# WatchDog.net
KiCad netlist of a schematic drawn in Altium Designer
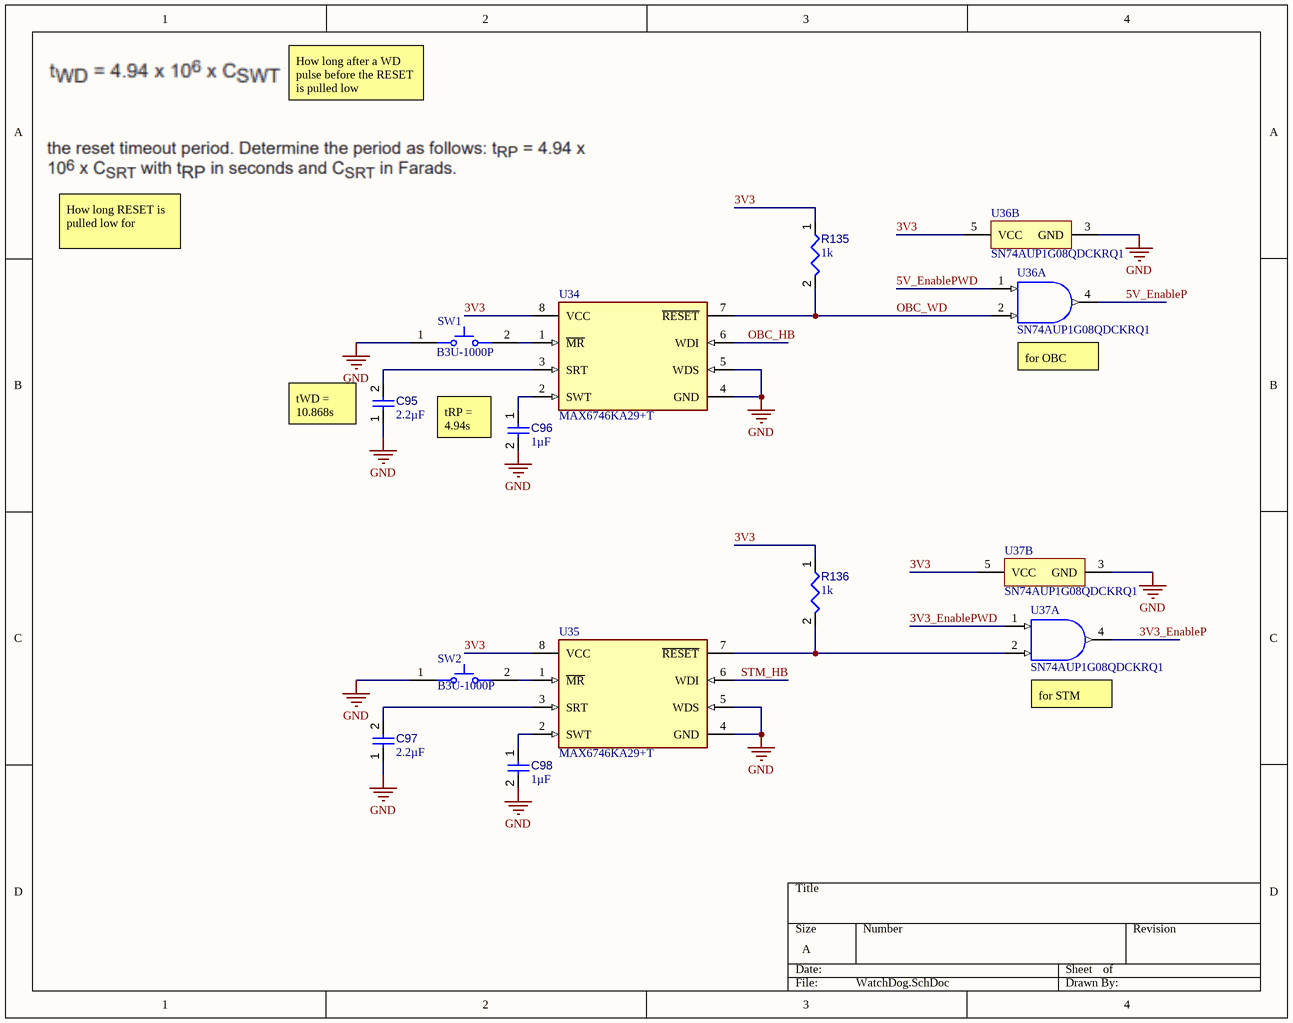
[diagram p0: WatchDog.SchDoc]

(export (version "E")
  (design (tool "Eeschema 10.0.6"))
  (components
    (comp (ref "C95")
      (value "2.2µF")
      (footprint "CAPC0402(1005)60_L")
      (description "Chip Capacitor, 2,2µF +/-20%, 10V, 0402, Thickness 0.6 mm")
      (fields (field (name "TOLERANCE") "10%") (field (name "Comment") "Capacitor 2,2µF +/-20% 10V 0402"))
      (libsource (lib "UGA SSRL Hardware Team") (part "CAP-NP-2"))
    )
    (comp (ref "C96")
      (value "1µF")
      (footprint "CAPC0603(1608)100_L")
      (description "Chip Capacitor, 1µF +/-40%, 50V, 0603, Thickness 1 mm")
      (fields (field (name "TOLERANCE") "10%") (field (name "Comment") "Capacitor 1µF +/-40% 50V 0603"))
      (libsource (lib "UGA SSRL Hardware Team") (part "CAP-NP-2"))
    )
    (comp (ref "C97")
      (value "2.2µF")
      (footprint "CAPC0402(1005)60_L")
      (description "Chip Capacitor, 2,2µF +/-20%, 10V, 0402, Thickness 0.6 mm")
      (fields (field (name "TOLERANCE") "10%") (field (name "Comment") "Capacitor 2,2µF +/-20% 10V 0402"))
      (libsource (lib "UGA SSRL Hardware Team") (part "CAP-NP-2"))
    )
    (comp (ref "C98")
      (value "1µF")
      (footprint "CAPC0603(1608)100_L")
      (description "Chip Capacitor, 1µF +/-40%, 50V, 0603, Thickness 1 mm")
      (fields (field (name "TOLERANCE") "10%") (field (name "Comment") "Capacitor 1µF +/-40% 50V 0603"))
      (libsource (lib "UGA SSRL Hardware Team") (part "CAP-NP-2"))
    )
    (comp (ref "R135")
      (value "1k")
      (footprint "RESC0805(2012)_L")
      (description "1K 0.125W 5% 0805 (2012 Metric)  SMD")
      (fields (field (name "TOLERANCE") "5%") (field (name "POWER") "125mW"))
      (libsource (lib "UGA SSRL Hardware Team") (part "1KR5J"))
    )
    (comp (ref "R136")
      (value "1k")
      (footprint "RESC0805(2012)_L")
      (description "1K 0.125W 5% 0805 (2012 Metric)  SMD")
      (fields (field (name "TOLERANCE") "5%") (field (name "POWER") "125mW"))
      (libsource (lib "UGA SSRL Hardware Team") (part "1KR5J"))
    )
    (comp (ref "SW1")
      (value "B3U-1000P")
      (footprint "OMRON-B3U-1000_V")
      (description "Tactile Switch, SPST-NO, 0.05 A, 12 V, -25 to 70 degC, 2-Pin SMD, RoHS, Tape and Reel")
      (fields (field (name "MANUFACTURER") "Omron Electronic Components"))
      (libsource (lib "UGA SSRL Hardware Team") (part "SW-SPST-NO-2"))
    )
    (comp (ref "SW2")
      (value "B3U-1000P")
      (footprint "OMRON-B3U-1000_V")
      (description "Tactile Switch, SPST-NO, 0.05 A, 12 V, -25 to 70 degC, 2-Pin SMD, RoHS, Tape and Reel")
      (fields (field (name "MANUFACTURER") "Omron Electronic Components"))
      (libsource (lib "UGA SSRL Hardware Team") (part "SW-SPST-NO-2"))
    )
    (comp (ref "U34")
      (value "MAX6746KA29+T")
      (footprint "FP-K8-5-IPC_C")
      (description "Power Supply Management Circuit, Adjustable, 1 Channel, BICMOS, PDSO8")
      (libsource (lib "UGA SSRL Hardware Team") (part "08e5617605ea42384b69bce613a8bab"))
    )
    (comp (ref "U35")
      (value "MAX6746KA29+T")
      (footprint "FP-K8-5-IPC_C")
      (description "Power Supply Management Circuit, Adjustable, 1 Channel, BICMOS, PDSO8")
      (libsource (lib "UGA SSRL Hardware Team") (part "08e5617605ea42384b69bce613a8bab"))
    )
    (comp (ref "U36")
      (value "SN74AUP1G08QDCKRQ1")
      (footprint "DCK0005A_N")
      (description "AND Gate, AUP/ULP/V Series, 1-Func, 2-Input, CMOS, PDSO5")
      (libsource (lib "UGA SSRL Hardware Team") (part "TI-SN74XXX1X08-5"))
    )
    (comp (ref "U37")
      (value "SN74AUP1G08QDCKRQ1")
      (footprint "DCK0005A_N")
      (description "AND Gate, AUP/ULP/V Series, 1-Func, 2-Input, CMOS, PDSO5")
      (libsource (lib "UGA SSRL Hardware Team") (part "TI-SN74XXX1X08-5"))
    )
  )
  (nets
    (net (code "1") (name "/3V3") (class "Default")
      (node (ref "R135") (pin "1") (pinfunction "1_1") (pintype "passive"))
      (node (ref "R136") (pin "1") (pinfunction "1_1") (pintype "passive"))
      (node (ref "U34") (pin "8") (pinfunction "VCC_8") (pintype "power_in"))
      (node (ref "U35") (pin "8") (pinfunction "VCC_8") (pintype "power_in"))
      (node (ref "U36") (pin "5") (pinfunction "VCC_5") (pintype "power_in"))
      (node (ref "U37") (pin "5") (pinfunction "VCC_5") (pintype "power_in"))
    )
    (net (code "2") (name "/3V3_EnableP") (class "Default")
      (node (ref "U37") (pin "4") (pinfunction "Y_4") (pintype "output"))
    )
    (net (code "3") (name "/3V3_EnablePWD") (class "Default")
      (node (ref "U37") (pin "1") (pinfunction "A_1") (pintype "input"))
    )
    (net (code "4") (name "/5V_EnableP") (class "Default")
      (node (ref "U36") (pin "4") (pinfunction "Y_4") (pintype "output"))
    )
    (net (code "5") (name "/5V_EnablePWD") (class "Default")
      (node (ref "U36") (pin "1") (pinfunction "A_1") (pintype "input"))
    )
    (net (code "6") (name "/OBC_HB") (class "Default")
      (node (ref "U34") (pin "6") (pinfunction "WDI_6") (pintype "input"))
    )
    (net (code "7") (name "/OBC_WD") (class "Default")
      (node (ref "R135") (pin "2") (pinfunction "2_2") (pintype "passive"))
      (node (ref "U34") (pin "7") (pinfunction "~{RESET}_7") (pintype "open_collector"))
      (node (ref "U36") (pin "2") (pinfunction "B_2") (pintype "input"))
    )
    (net (code "8") (name "/STM_HB") (class "Default")
      (node (ref "U35") (pin "6") (pinfunction "WDI_6") (pintype "input"))
    )
    (net (code "9") (name "GND") (class "Default")
      (node (ref "C95") (pin "1") (pinfunction "1_1") (pintype "passive"))
      (node (ref "C96") (pin "2") (pinfunction "2_2") (pintype "passive"))
      (node (ref "C97") (pin "1") (pinfunction "1_1") (pintype "passive"))
      (node (ref "C98") (pin "2") (pinfunction "2_2") (pintype "passive"))
      (node (ref "SW1") (pin "1") (pinfunction "1_1") (pintype "passive"))
      (node (ref "SW2") (pin "1") (pinfunction "1_1") (pintype "passive"))
      (node (ref "U34") (pin "4") (pinfunction "GND_4") (pintype "power_in"))
      (node (ref "U34") (pin "5") (pinfunction "WDS_5") (pintype "input"))
      (node (ref "U35") (pin "4") (pinfunction "GND_4") (pintype "power_in"))
      (node (ref "U35") (pin "5") (pinfunction "WDS_5") (pintype "input"))
      (node (ref "U36") (pin "3") (pinfunction "GND_3") (pintype "power_in"))
      (node (ref "U37") (pin "3") (pinfunction "GND_3") (pintype "power_in"))
    )
    (net (code "10") (name "Net-(U34-SRT)") (class "Default")
      (node (ref "C95") (pin "2") (pinfunction "2_2") (pintype "passive"))
      (node (ref "U34") (pin "3") (pinfunction "SRT_3") (pintype "input"))
    )
    (net (code "11") (name "Net-(U34-SWT)") (class "Default")
      (node (ref "C96") (pin "1") (pinfunction "1_1") (pintype "passive"))
      (node (ref "U34") (pin "2") (pinfunction "SWT_2") (pintype "input"))
    )
    (net (code "12") (name "Net-(U34-~{MR})") (class "Default")
      (node (ref "SW1") (pin "2") (pinfunction "2_2") (pintype "passive"))
      (node (ref "U34") (pin "1") (pinfunction "~{MR}_1") (pintype "input"))
    )
    (net (code "13") (name "Net-(U35-SRT)") (class "Default")
      (node (ref "C97") (pin "2") (pinfunction "2_2") (pintype "passive"))
      (node (ref "U35") (pin "3") (pinfunction "SRT_3") (pintype "input"))
    )
    (net (code "14") (name "Net-(U35-SWT)") (class "Default")
      (node (ref "C98") (pin "1") (pinfunction "1_1") (pintype "passive"))
      (node (ref "U35") (pin "2") (pinfunction "SWT_2") (pintype "input"))
    )
    (net (code "15") (name "Net-(U35-~{MR})") (class "Default")
      (node (ref "SW2") (pin "2") (pinfunction "2_2") (pintype "passive"))
      (node (ref "U35") (pin "1") (pinfunction "~{MR}_1") (pintype "input"))
    )
    (net (code "16") (name "Net-(U35-~{RESET})") (class "Default")
      (node (ref "R136") (pin "2") (pinfunction "2_2") (pintype "passive"))
      (node (ref "U35") (pin "7") (pinfunction "~{RESET}_7") (pintype "open_collector"))
      (node (ref "U37") (pin "2") (pinfunction "B_2") (pintype "input"))
    )
  )
)
